# ar_env.net
KiCad netlist of a schematic drawn in EAGLE
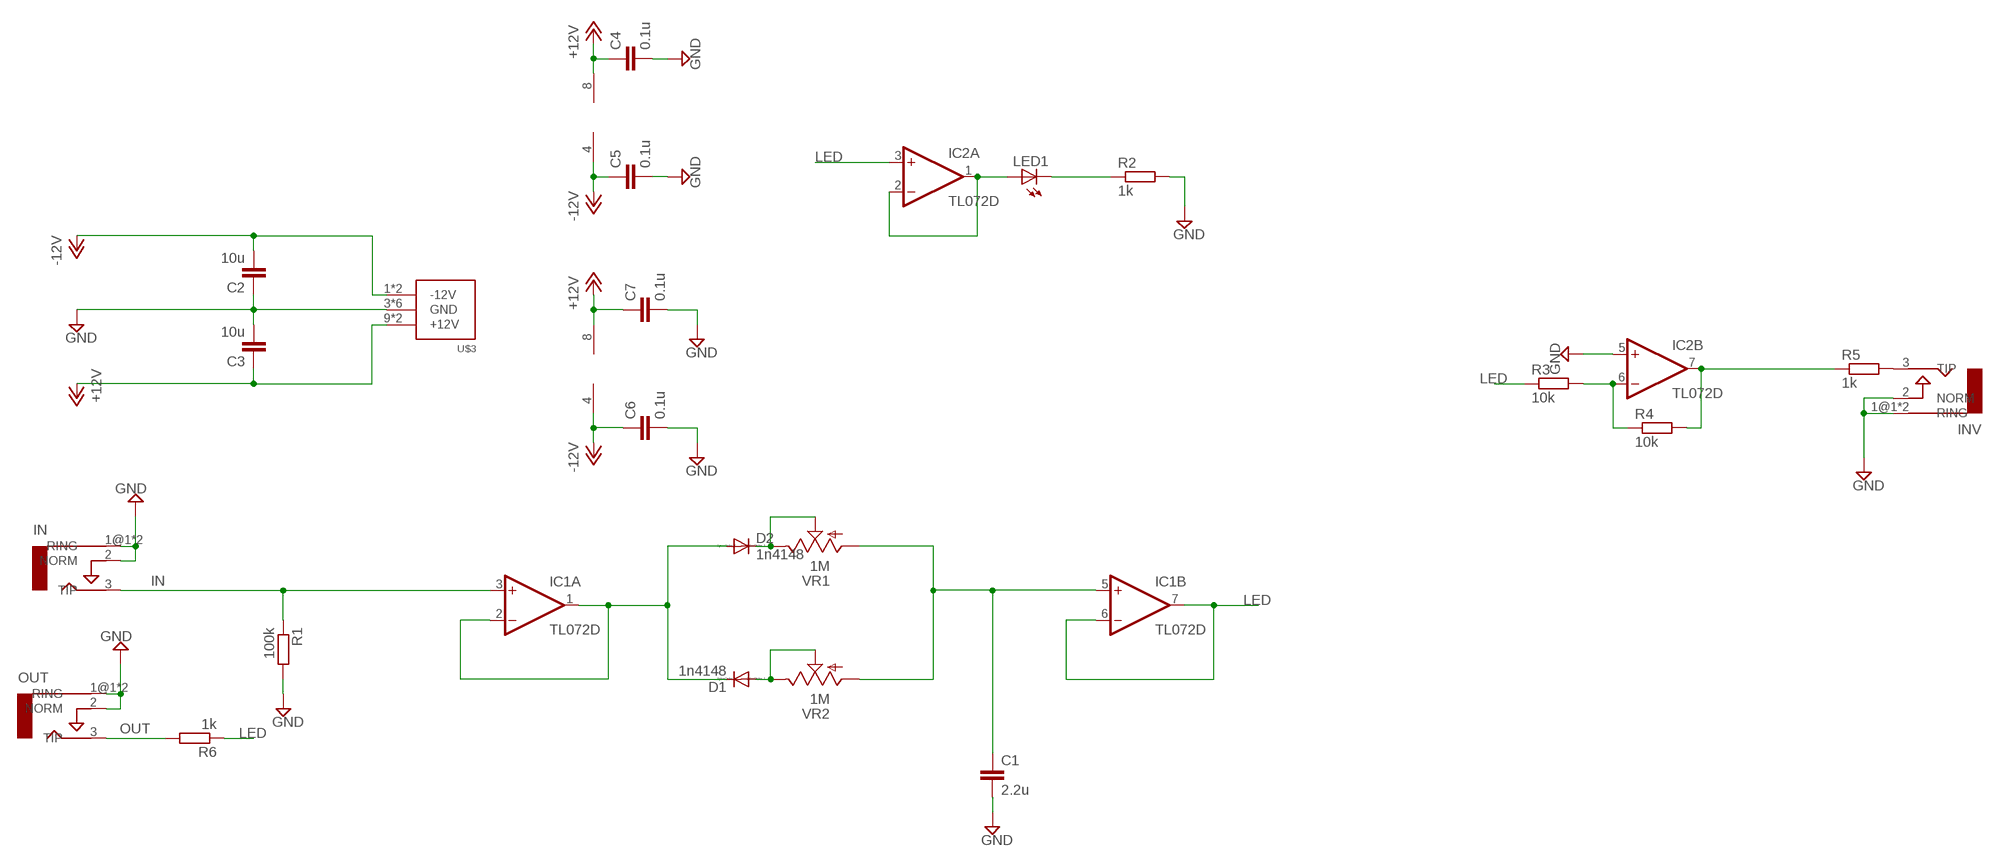
[diagram p0: schematic, sheet 1]

(export (version "E")
  (design (tool "Eeschema 10.0.6"))
  (components
    (comp (ref "C1")
      (value "2.2u")
      (footprint "eagle-import:C0805")
      (libsource (lib "eagle-import") (part "C-EUC0805"))
    )
    (comp (ref "C2")
      (value "10u")
      (footprint "eagle-import:C0805")
      (libsource (lib "eagle-import") (part "C-EUC0805"))
    )
    (comp (ref "C3")
      (value "10u")
      (footprint "eagle-import:C0805")
      (libsource (lib "eagle-import") (part "C-EUC0805"))
    )
    (comp (ref "C4")
      (value "0.1u")
      (footprint "eagle-import:C0805")
      (libsource (lib "eagle-import") (part "C-EUC0805"))
    )
    (comp (ref "C5")
      (value "0.1u")
      (footprint "eagle-import:C0805")
      (libsource (lib "eagle-import") (part "C-EUC0805"))
    )
    (comp (ref "C6")
      (value "0.1u")
      (footprint "eagle-import:C0805")
      (libsource (lib "eagle-import") (part "C-EUC0805"))
    )
    (comp (ref "C7")
      (value "0.1u")
      (footprint "eagle-import:C0805")
      (libsource (lib "eagle-import") (part "C-EUC0805"))
    )
    (comp (ref "D1")
      (value "1n4148")
      (footprint "eagle-import:SOD323-W")
      (libsource (lib "eagle-import") (part "DIODE-SOD323-W"))
    )
    (comp (ref "D2")
      (value "1n4148")
      (footprint "eagle-import:SOD323-W")
      (libsource (lib "eagle-import") (part "DIODE-SOD323-W"))
    )
    (comp (ref "IC1")
      (value "TL072D")
      (footprint "eagle-import:SO08")
      (libsource (lib "eagle-import") (part "TL072D"))
    )
    (comp (ref "IC2")
      (value "TL072D")
      (footprint "eagle-import:SO08")
      (libsource (lib "eagle-import") (part "TL072D"))
    )
    (comp (ref "IN")
      (value "AUDIO-JACKERTHENVAR")
      (footprint "eagle-import:ERTHENVAR-JACK")
      (libsource (lib "eagle-import") (part "AUDIO-JACKERTHENVAR"))
    )
    (comp (ref "INV")
      (value "AUDIO-JACKERTHENVAR")
      (footprint "eagle-import:ERTHENVAR-JACK")
      (libsource (lib "eagle-import") (part "AUDIO-JACKERTHENVAR"))
    )
    (comp (ref "LED1")
      (value "LEDCHIP-LED0805")
      (footprint "eagle-import:CHIP-LED0805")
      (libsource (lib "eagle-import") (part "LEDCHIP-LED0805"))
    )
    (comp (ref "OUT")
      (value "AUDIO-JACKERTHENVAR")
      (footprint "eagle-import:ERTHENVAR-JACK")
      (libsource (lib "eagle-import") (part "AUDIO-JACKERTHENVAR"))
    )
    (comp (ref "R1")
      (value "100k")
      (footprint "eagle-import:R0805")
      (libsource (lib "eagle-import") (part "R-EU_R0805"))
    )
    (comp (ref "R2")
      (value "1k")
      (footprint "eagle-import:R0805")
      (libsource (lib "eagle-import") (part "R-EU_R0805"))
    )
    (comp (ref "R3")
      (value "10k")
      (footprint "eagle-import:R0805")
      (libsource (lib "eagle-import") (part "R-EU_R0805"))
    )
    (comp (ref "R4")
      (value "10k")
      (footprint "eagle-import:R0805")
      (libsource (lib "eagle-import") (part "R-EU_R0805"))
    )
    (comp (ref "R5")
      (value "1k")
      (footprint "eagle-import:R0805")
      (libsource (lib "eagle-import") (part "R-EU_R0805"))
    )
    (comp (ref "R6")
      (value "1k")
      (footprint "eagle-import:R0805")
      (libsource (lib "eagle-import") (part "R-EU_R0805"))
    )
    (comp (ref "U$3")
      (value "POWER_SIMPLE10")
      (footprint "eagle-import:POWER_10")
      (libsource (lib "eagle-import") (part "POWER_SIMPLE10"))
    )
    (comp (ref "VR1")
      (value "1M")
      (footprint "eagle-import:9MM_SNAP-IN_POT")
      (libsource (lib "eagle-import") (part "9MM_SNAP-IN_POT_"))
    )
    (comp (ref "VR2")
      (value "1M")
      (footprint "eagle-import:9MM_SNAP-IN_POT")
      (libsource (lib "eagle-import") (part "9MM_SNAP-IN_POT_"))
    )
  )
  (nets
    (net (code "1") (name "+12V") (class "Default")
      (node (ref "C3") (pin "1") (pinfunction "1_1") (pintype "passive"))
      (node (ref "C4") (pin "1") (pinfunction "1_1") (pintype "passive"))
      (node (ref "C7") (pin "1") (pinfunction "1_1") (pintype "passive"))
      (node (ref "IC1") (pin "8") (pinfunction "V+_8") (pintype "power_in"))
      (node (ref "IC2") (pin "8") (pinfunction "V+_8") (pintype "power_in"))
      (node (ref "U$3") (pin "10") (pinfunction "+12V_10") (pintype "bidirectional"))
      (node (ref "U$3") (pin "9") (pinfunction "+12V_9") (pintype "bidirectional"))
    )
    (net (code "2") (name "-12V") (class "Default")
      (node (ref "C2") (pin "2") (pinfunction "2_2") (pintype "passive"))
      (node (ref "C5") (pin "1") (pinfunction "1_1") (pintype "passive"))
      (node (ref "C6") (pin "1") (pinfunction "1_1") (pintype "passive"))
      (node (ref "IC1") (pin "4") (pinfunction "V-_4") (pintype "power_in"))
      (node (ref "IC2") (pin "4") (pinfunction "V-_4") (pintype "power_in"))
      (node (ref "U$3") (pin "1") (pinfunction "-12V_1") (pintype "bidirectional"))
      (node (ref "U$3") (pin "2") (pinfunction "-12V_2") (pintype "bidirectional"))
    )
    (net (code "3") (name "/IN") (class "Default")
      (node (ref "IC1") (pin "3") (pinfunction "+IN_3") (pintype "input"))
      (node (ref "IN") (pin "3") (pinfunction "TIP_3") (pintype "bidirectional"))
      (node (ref "R1") (pin "1") (pinfunction "1_1") (pintype "passive"))
    )
    (net (code "4") (name "/LED") (class "Default")
      (node (ref "IC1") (pin "6") (pinfunction "-IN_6") (pintype "input"))
      (node (ref "IC1") (pin "7") (pinfunction "OUT_7") (pintype "output"))
      (node (ref "IC2") (pin "3") (pinfunction "+IN_3") (pintype "input"))
      (node (ref "R3") (pin "1") (pinfunction "1_1") (pintype "passive"))
      (node (ref "R6") (pin "1") (pinfunction "1_1") (pintype "passive"))
    )
    (net (code "5") (name "/OUT") (class "Default")
      (node (ref "OUT") (pin "3") (pinfunction "TIP_3") (pintype "bidirectional"))
      (node (ref "R6") (pin "2") (pinfunction "2_2") (pintype "passive"))
    )
    (net (code "6") (name "GND") (class "Default")
      (node (ref "C1") (pin "2") (pinfunction "2_2") (pintype "passive"))
      (node (ref "C2") (pin "1") (pinfunction "1_1") (pintype "passive"))
      (node (ref "C3") (pin "2") (pinfunction "2_2") (pintype "passive"))
      (node (ref "C4") (pin "2") (pinfunction "2_2") (pintype "passive"))
      (node (ref "C5") (pin "2") (pinfunction "2_2") (pintype "passive"))
      (node (ref "C6") (pin "2") (pinfunction "2_2") (pintype "passive"))
      (node (ref "C7") (pin "2") (pinfunction "2_2") (pintype "passive"))
      (node (ref "IC2") (pin "5") (pinfunction "+IN_5") (pintype "input"))
      (node (ref "IN") (pin "1@1") (pinfunction "RING_1@1") (pintype "bidirectional"))
      (node (ref "IN") (pin "1@2") (pinfunction "RING_1@2") (pintype "bidirectional"))
      (node (ref "IN") (pin "2") (pinfunction "NORM_2") (pintype "bidirectional"))
      (node (ref "INV") (pin "1@1") (pinfunction "RING_1@1") (pintype "bidirectional"))
      (node (ref "INV") (pin "1@2") (pinfunction "RING_1@2") (pintype "bidirectional"))
      (node (ref "INV") (pin "2") (pinfunction "NORM_2") (pintype "bidirectional"))
      (node (ref "OUT") (pin "1@1") (pinfunction "RING_1@1") (pintype "bidirectional"))
      (node (ref "OUT") (pin "1@2") (pinfunction "RING_1@2") (pintype "bidirectional"))
      (node (ref "OUT") (pin "2") (pinfunction "NORM_2") (pintype "bidirectional"))
      (node (ref "R1") (pin "2") (pinfunction "2_2") (pintype "passive"))
      (node (ref "R2") (pin "2") (pinfunction "2_2") (pintype "passive"))
      (node (ref "U$3") (pin "3") (pinfunction "GND_3") (pintype "bidirectional"))
      (node (ref "U$3") (pin "4") (pinfunction "GND_4") (pintype "bidirectional"))
      (node (ref "U$3") (pin "5") (pinfunction "GND_5") (pintype "bidirectional"))
      (node (ref "U$3") (pin "6") (pinfunction "GND_6") (pintype "bidirectional"))
      (node (ref "U$3") (pin "7") (pinfunction "GND_7") (pintype "bidirectional"))
      (node (ref "U$3") (pin "8") (pinfunction "GND_8") (pintype "bidirectional"))
    )
    (net (code "7") (name "Net-(IC1A--IN)") (class "Default")
      (node (ref "D1") (pin "C") (pinfunction "C_C") (pintype "passive"))
      (node (ref "D2") (pin "A") (pinfunction "A_A") (pintype "passive"))
      (node (ref "IC1") (pin "1") (pinfunction "OUT_1") (pintype "output"))
      (node (ref "IC1") (pin "2") (pinfunction "-IN_2") (pintype "input"))
    )
    (net (code "8") (name "Net-(IC1B-+IN)") (class "Default")
      (node (ref "C1") (pin "1") (pinfunction "1_1") (pintype "passive"))
      (node (ref "IC1") (pin "5") (pinfunction "+IN_5") (pintype "input"))
      (node (ref "VR1") (pin "1") (pinfunction "A_1") (pintype "passive"))
      (node (ref "VR2") (pin "1") (pinfunction "A_1") (pintype "passive"))
    )
    (net (code "9") (name "Net-(IC2A--IN)") (class "Default")
      (node (ref "IC2") (pin "1") (pinfunction "OUT_1") (pintype "output"))
      (node (ref "IC2") (pin "2") (pinfunction "-IN_2") (pintype "input"))
      (node (ref "LED1") (pin "A") (pinfunction "A_A") (pintype "passive"))
    )
    (net (code "10") (name "Net-(IC2B--IN)") (class "Default")
      (node (ref "IC2") (pin "6") (pinfunction "-IN_6") (pintype "input"))
      (node (ref "R3") (pin "2") (pinfunction "2_2") (pintype "passive"))
      (node (ref "R4") (pin "1") (pinfunction "1_1") (pintype "passive"))
    )
    (net (code "11") (name "Net-(IC2B-OUT)") (class "Default")
      (node (ref "IC2") (pin "7") (pinfunction "OUT_7") (pintype "output"))
      (node (ref "R4") (pin "2") (pinfunction "2_2") (pintype "passive"))
      (node (ref "R5") (pin "1") (pinfunction "1_1") (pintype "passive"))
    )
    (net (code "12") (name "Net-(INV-TIP)") (class "Default")
      (node (ref "INV") (pin "3") (pinfunction "TIP_3") (pintype "bidirectional"))
      (node (ref "R5") (pin "2") (pinfunction "2_2") (pintype "passive"))
    )
    (net (code "13") (name "Net-(LED1-PadC)") (class "Default")
      (node (ref "LED1") (pin "C") (pinfunction "C_C") (pintype "passive"))
      (node (ref "R2") (pin "1") (pinfunction "1_1") (pintype "passive"))
    )
    (net (code "14") (name "Net-(VR1-E)") (class "Default")
      (node (ref "D2") (pin "C") (pinfunction "C_C") (pintype "passive"))
      (node (ref "VR1") (pin "2") (pinfunction "S_2") (pintype "passive"))
      (node (ref "VR1") (pin "3") (pinfunction "E_3") (pintype "passive"))
    )
    (net (code "15") (name "Net-(VR2-E)") (class "Default")
      (node (ref "D1") (pin "A") (pinfunction "A_A") (pintype "passive"))
      (node (ref "VR2") (pin "2") (pinfunction "S_2") (pintype "passive"))
      (node (ref "VR2") (pin "3") (pinfunction "E_3") (pintype "passive"))
    )
  )
)
